# Arduino.net
KiCad netlist of a schematic drawn in Altium Designer
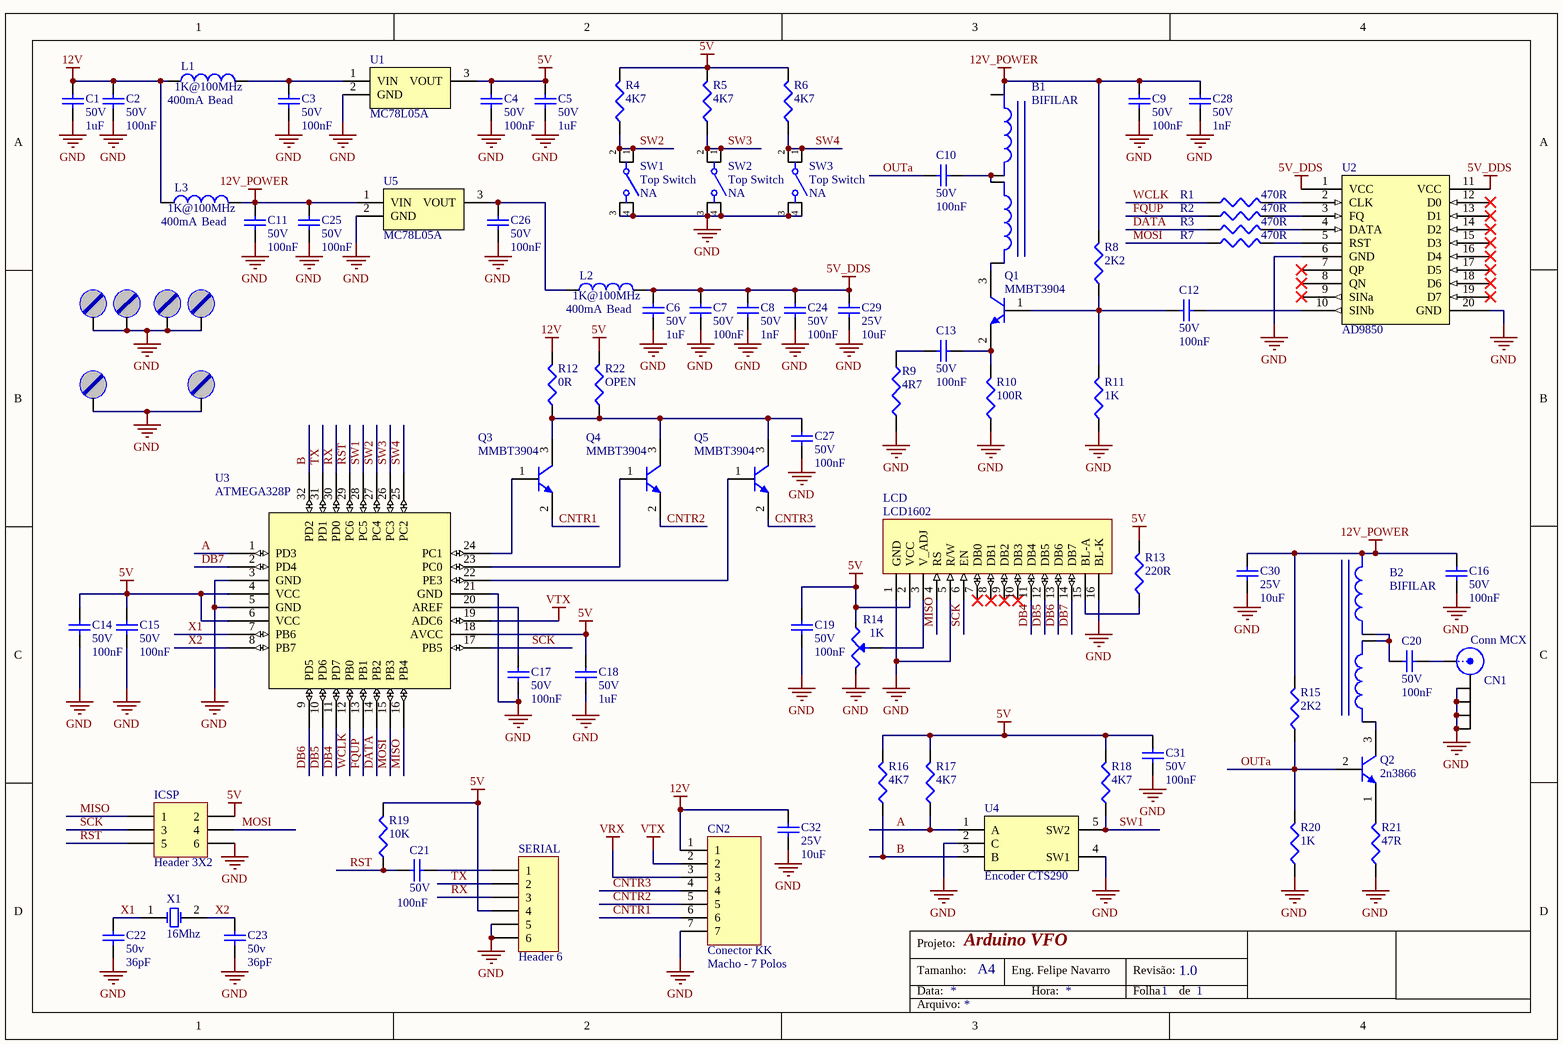
[diagram p0: Arduino.SchDoc]

(export (version "E")
  (design (tool "Eeschema 10.0.6"))
  (components
    (comp (ref "B1")
      (value "BIFILAR")
      (footprint "Toroid Bifilar")
      (description "Toroid Bifilar")
      (libsource (lib "") (part "Toroid Bifilar_1"))
    )
    (comp (ref "B2")
      (value "BIFILAR")
      (footprint "Toroid Bifilar")
      (description "Toroid Bifilar")
      (libsource (lib "NavarroIND") (part "Toroid Bifilar"))
    )
    (comp (ref "C1")
      (value "1uF")
      (footprint "CC0603")
      (description "Capacitor (Semiconductor SIM Model)")
      (fields (field (name "TENSÃO") "50V") (field (name "Comment") "Capacitor Cerâmico"))
      (libsource (lib "NavarroCAP") (part "Cap 1uF 50V 0603 X5R"))
    )
    (comp (ref "C2")
      (value "100nF")
      (footprint "CC0603")
      (description "Capacitor (Semiconductor SIM Model)")
      (fields (field (name "TENSÃO") "50V") (field (name "Comment") "Capacitor Cerâmico"))
      (libsource (lib "NavarroCAP") (part "Cap 100nF 50V 0603 X7R"))
    )
    (comp (ref "C3")
      (value "100nF")
      (footprint "CC0603")
      (description "Capacitor (Semiconductor SIM Model)")
      (fields (field (name "TENSÃO") "50V") (field (name "Comment") "Capacitor Cerâmico"))
      (libsource (lib "NavarroCAP") (part "Cap 100nF 50V 0603 X7R"))
    )
    (comp (ref "C4")
      (value "100nF")
      (footprint "CC0603")
      (description "Capacitor (Semiconductor SIM Model)")
      (fields (field (name "TENSÃO") "50V") (field (name "Comment") "Capacitor Cerâmico"))
      (libsource (lib "NavarroCAP") (part "Cap 100nF 50V 0603 X7R"))
    )
    (comp (ref "C5")
      (value "1uF")
      (footprint "CC0603")
      (description "Capacitor (Semiconductor SIM Model)")
      (fields (field (name "TENSÃO") "50V") (field (name "Comment") "Capacitor Cerâmico"))
      (libsource (lib "NavarroCAP") (part "Cap 1uF 50V 0603 X5R"))
    )
    (comp (ref "C6")
      (value "1uF")
      (footprint "CC0603")
      (description "Capacitor (Semiconductor SIM Model)")
      (fields (field (name "TENSÃO") "50V") (field (name "Comment") "Capacitor Cerâmico"))
      (libsource (lib "NavarroCAP") (part "Cap 1uF 50V 0603 X5R"))
    )
    (comp (ref "C7")
      (value "100nF")
      (footprint "CC0603")
      (description "Capacitor (Semiconductor SIM Model)")
      (fields (field (name "TENSÃO") "50V") (field (name "Comment") "Capacitor Cerâmico"))
      (libsource (lib "NavarroCAP") (part "Cap 100nF 50V 0603 X7R"))
    )
    (comp (ref "C8")
      (value "1nF")
      (footprint "CC0603")
      (description "Capacitor (Semiconductor SIM Model)")
      (fields (field (name "TENSÃO") "50V") (field (name "Comment") "Capacitor Cerâmico"))
      (libsource (lib "NavarroCAP") (part "Cap 1nF 50V 0603 NP0"))
    )
    (comp (ref "C9")
      (value "100nF")
      (footprint "CC0603")
      (description "Capacitor (Semiconductor SIM Model)")
      (fields (field (name "TENSÃO") "50V") (field (name "Comment") "Capacitor Cerâmico"))
      (libsource (lib "NavarroCAP") (part "Cap 100nF 50V 0603 X7R"))
    )
    (comp (ref "C10")
      (value "100nF")
      (footprint "CC0603")
      (description "Capacitor (Semiconductor SIM Model)")
      (fields (field (name "TENSÃO") "50V") (field (name "Comment") "Capacitor Cerâmico"))
      (libsource (lib "NavarroCAP") (part "Cap 100nF 50V 0603 X7R"))
    )
    (comp (ref "C11")
      (value "100nF")
      (footprint "CC0603")
      (description "Capacitor (Semiconductor SIM Model)")
      (fields (field (name "TENSÃO") "50V") (field (name "Comment") "Capacitor Cerâmico"))
      (libsource (lib "NavarroCAP") (part "Cap 100nF 50V 0603 X7R"))
    )
    (comp (ref "C12")
      (value "100nF")
      (footprint "CC0603")
      (description "Capacitor (Semiconductor SIM Model)")
      (fields (field (name "TENSÃO") "50V") (field (name "Comment") "Capacitor Cerâmico"))
      (libsource (lib "NavarroCAP") (part "Cap 100nF 50V 0603 X7R"))
    )
    (comp (ref "C13")
      (value "100nF")
      (footprint "CC0603")
      (description "Capacitor (Semiconductor SIM Model)")
      (fields (field (name "TENSÃO") "50V") (field (name "Comment") "Capacitor Cerâmico"))
      (libsource (lib "NavarroCAP") (part "Cap 100nF 50V 0603 X7R"))
    )
    (comp (ref "C14")
      (value "100nF")
      (footprint "CC0603")
      (description "Capacitor (Semiconductor SIM Model)")
      (fields (field (name "TENSÃO") "50V") (field (name "Comment") "Capacitor Cerâmico"))
      (libsource (lib "NavarroCAP") (part "Cap 100nF 50V 0603 X7R"))
    )
    (comp (ref "C15")
      (value "100nF")
      (footprint "CC0603")
      (description "Capacitor (Semiconductor SIM Model)")
      (fields (field (name "TENSÃO") "50V") (field (name "Comment") "Capacitor Cerâmico"))
      (libsource (lib "NavarroCAP") (part "Cap 100nF 50V 0603 X7R"))
    )
    (comp (ref "C16")
      (value "100nF")
      (footprint "CC0603")
      (description "Capacitor (Semiconductor SIM Model)")
      (fields (field (name "TENSÃO") "50V") (field (name "Comment") "Capacitor Cerâmico"))
      (libsource (lib "NavarroCAP") (part "Cap 100nF 50V 0603 X7R"))
    )
    (comp (ref "C17")
      (value "100nF")
      (footprint "CC0603")
      (description "Capacitor (Semiconductor SIM Model)")
      (fields (field (name "TENSÃO") "50V") (field (name "Comment") "Capacitor Cerâmico"))
      (libsource (lib "NavarroCAP") (part "Cap 100nF 50V 0603 X7R"))
    )
    (comp (ref "C18")
      (value "1uF")
      (footprint "CC0603")
      (description "Capacitor (Semiconductor SIM Model)")
      (fields (field (name "TENSÃO") "50V") (field (name "Comment") "Capacitor Cerâmico"))
      (libsource (lib "NavarroCAP") (part "Cap 1uF 50V 0603 X5R"))
    )
    (comp (ref "C19")
      (value "100nF")
      (footprint "CC0603")
      (description "Capacitor (Semiconductor SIM Model)")
      (fields (field (name "TENSÃO") "50V") (field (name "Comment") "Capacitor Cerâmico"))
      (libsource (lib "NavarroCAP") (part "Cap 100nF 50V 0603 X7R"))
    )
    (comp (ref "C20")
      (value "100nF")
      (footprint "CC0603")
      (description "Capacitor (Semiconductor SIM Model)")
      (fields (field (name "TENSÃO") "50V") (field (name "Comment") "Capacitor Cerâmico"))
      (libsource (lib "NavarroCAP") (part "Cap 100nF 50V 0603 X7R"))
    )
    (comp (ref "C21")
      (value "100nF")
      (footprint "CC0603")
      (description "Capacitor (Semiconductor SIM Model)")
      (fields (field (name "TENSÃO") "50V") (field (name "Comment") "Capacitor Cerâmico"))
      (libsource (lib "NavarroCAP") (part "Cap 100nF 50V 0603 X7R"))
    )
    (comp (ref "C22")
      (value "36pF")
      (footprint "CC0603")
      (description "Capacitor (Semiconductor SIM Model)")
      (fields (field (name "TENSÃO") "50v") (field (name "Comment") "Capacitor Cerâmico"))
      (libsource (lib "NavarroCAP") (part "Cap - $Val $V $Footprint $Classe_1"))
    )
    (comp (ref "C23")
      (value "36pF")
      (footprint "CC0603")
      (description "Capacitor (Semiconductor SIM Model)")
      (fields (field (name "TENSÃO") "50v") (field (name "Comment") "Capacitor Cerâmico"))
      (libsource (lib "NavarroCAP") (part "Cap - $Val $V $Footprint $Classe_1"))
    )
    (comp (ref "C24")
      (value "100nF")
      (footprint "CC0603")
      (description "Capacitor (Semiconductor SIM Model)")
      (fields (field (name "TENSÃO") "50V") (field (name "Comment") "Capacitor Cerâmico"))
      (libsource (lib "NavarroCAP") (part "Cap 100nF 50V 0603 X7R"))
    )
    (comp (ref "C25")
      (value "100nF")
      (footprint "CC0603")
      (description "Capacitor (Semiconductor SIM Model)")
      (fields (field (name "TENSÃO") "50V") (field (name "Comment") "Capacitor Cerâmico"))
      (libsource (lib "NavarroCAP") (part "Cap 100nF 50V 0603 X7R"))
    )
    (comp (ref "C26")
      (value "100nF")
      (footprint "CC0603")
      (description "Capacitor (Semiconductor SIM Model)")
      (fields (field (name "TENSÃO") "50V") (field (name "Comment") "Capacitor Cerâmico"))
      (libsource (lib "NavarroCAP") (part "Cap 100nF 50V 0603 X7R"))
    )
    (comp (ref "C27")
      (value "100nF")
      (footprint "CC0603")
      (description "Capacitor (Semiconductor SIM Model)")
      (fields (field (name "TENSÃO") "50V") (field (name "Comment") "Capacitor Cerâmico"))
      (libsource (lib "NavarroCAP") (part "Cap 100nF 50V 0603 X7R"))
    )
    (comp (ref "C28")
      (value "1nF")
      (footprint "CC0603")
      (description "Capacitor (Semiconductor SIM Model)")
      (fields (field (name "TENSÃO") "50V") (field (name "Comment") "Capacitor Cerâmico"))
      (libsource (lib "NavarroCAP") (part "Cap 100nF 50V 0603 X7R"))
    )
    (comp (ref "C29")
      (value "10uF")
      (footprint "CC0805")
      (description "Capacitor (Semiconductor SIM Model)")
      (fields (field (name "TENSÃO") "25V") (field (name "Comment") "Capacitor Cerâmico"))
      (libsource (lib "NavarroCAP") (part "Cap 10uF 25V 0805 X5R"))
    )
    (comp (ref "C30")
      (value "10uF")
      (footprint "CC0805")
      (description "Capacitor (Semiconductor SIM Model)")
      (fields (field (name "TENSÃO") "25V") (field (name "Comment") "Capacitor Cerâmico"))
      (libsource (lib "NavarroCAP") (part "Cap 10uF 25V 0805 X5R"))
    )
    (comp (ref "C31")
      (value "100nF")
      (footprint "CC0603")
      (description "Capacitor (Semiconductor SIM Model)")
      (fields (field (name "TENSÃO") "50V") (field (name "Comment") "Capacitor Cerâmico"))
      (libsource (lib "NavarroCAP") (part "Cap 100nF 50V 0603 X7R"))
    )
    (comp (ref "C32")
      (value "10uF")
      (footprint "CC0805")
      (description "Capacitor (Semiconductor SIM Model)")
      (fields (field (name "TENSÃO") "25V") (field (name "Comment") "Capacitor Cerâmico"))
      (libsource (lib "NavarroCAP") (part "Cap 10uF 25V 0805 X5R"))
    )
    (comp (ref "CN1")
      (value "Conn MCX")
      (footprint "CONN MCX MOLEX")
      (description "Conector MCX")
      (libsource (lib "NavarroCON") (part "Conn MCX"))
    )
    (comp (ref "CN2")
      (value "Conector KK")
      (footprint "CONN HDR7-POL P.100")
      (fields (field (name "ALTIUM_VALUE") "Macho - 7 Polos"))
      (libsource (lib "NavarroCON") (part "KK 7P Macho-V P2.54mm"))
    )
    (comp (ref "ICSP")
      (value "Header 3X2")
      (footprint "CONN HDR2X3")
      (description "Header, 5-Pin, Dual row")
      (libsource (lib "NavarroCON") (part "Header 3X2"))
    )
    (comp (ref "L1")
      (value "Bead")
      (footprint "CC0603")
      (fields (field (name "CORRENTE") "400mA") (field (name "ALTIUM_VALUE") "1K@100MHz"))
      (libsource (lib "NavarroIND") (part "Bd 1K@100MHz 0603 400mA"))
    )
    (comp (ref "L2")
      (value "Bead")
      (footprint "CC0603")
      (fields (field (name "CORRENTE") "400mA") (field (name "ALTIUM_VALUE") "1K@100MHz"))
      (libsource (lib "NavarroIND") (part "Bd 1K@100MHz 0603 400mA"))
    )
    (comp (ref "L3")
      (value "Bead")
      (footprint "CC0603")
      (fields (field (name "CORRENTE") "400mA") (field (name "ALTIUM_VALUE") "1K@100MHz"))
      (libsource (lib "NavarroIND") (part "Bd 1K@100MHz 0603 400mA"))
    )
    (comp (ref "LCD")
      (value "LCD1602")
      (footprint "LCD-1602")
      (description "LCD Generico 16 caracteres X 2 linhas")
      (libsource (lib "Navarro") (part "LCD1602"))
    )
    (comp (ref "M1")
      (value "Furo de Fixação")
      (footprint "Furo_M3")
      (description "Furo para parafuso")
      (libsource (lib "Tecnoclade") (part "Parafuso"))
    )
    (comp (ref "M2")
      (value "Furo de Fixação")
      (footprint "Furo_M3")
      (description "Furo para parafuso")
      (libsource (lib "Tecnoclade") (part "Parafuso"))
    )
    (comp (ref "M3")
      (value "Furo de Fixação")
      (footprint "Furo_M3")
      (description "Furo para parafuso")
      (libsource (lib "Tecnoclade") (part "Parafuso"))
    )
    (comp (ref "M4")
      (value "Furo de Fixação")
      (footprint "Furo_M3")
      (description "Furo para parafuso")
      (libsource (lib "Tecnoclade") (part "Parafuso"))
    )
    (comp (ref "M5")
      (value "Furo de Fixação")
      (footprint "Furo_M3")
      (description "Furo para parafuso")
      (libsource (lib "Tecnoclade") (part "Parafuso"))
    )
    (comp (ref "M6")
      (value "Furo de Fixação")
      (footprint "Furo_M3")
      (description "Furo para parafuso")
      (libsource (lib "Tecnoclade") (part "Parafuso"))
    )
    (comp (ref "Q1")
      (value "MMBT3904")
      (footprint "SOT-23-3N")
      (description "NPN General Purpose Amplifier")
      (libsource (lib "NavarroSEMI") (part "TRS MMBT3904 40V 200mA SOT-23-3N"))
    )
    (comp (ref "Q2")
      (value "2n3866")
      (footprint "TO-92R")
      (description "NPN General Purpose Amplifier")
      (libsource (lib "NavarroSEMI") (part "TRS BC108 TO-18"))
    )
    (comp (ref "Q3")
      (value "MMBT3904")
      (footprint "SOT-23-3N")
      (description "NPN General Purpose Amplifier")
      (libsource (lib "NavarroSEMI") (part "TRS MMBT3904 40V 200mA SOT-23-3N"))
    )
    (comp (ref "Q4")
      (value "MMBT3904")
      (footprint "SOT-23-3N")
      (description "NPN General Purpose Amplifier")
      (libsource (lib "NavarroSEMI") (part "TRS MMBT3904 40V 200mA SOT-23-3N"))
    )
    (comp (ref "Q5")
      (value "MMBT3904")
      (footprint "SOT-23-3N")
      (description "NPN General Purpose Amplifier")
      (libsource (lib "NavarroSEMI") (part "TRS MMBT3904 40V 200mA SOT-23-3N"))
    )
    (comp (ref "R1")
      (value "470R")
      (footprint "CC0603")
      (description "Resistor")
      (libsource (lib "NavarroRES") (part "Res 470R 5% 0603 1/10W"))
    )
    (comp (ref "R2")
      (value "470R")
      (footprint "CC0603")
      (description "Resistor")
      (libsource (lib "NavarroRES") (part "Res 470R 5% 0603 1/10W"))
    )
    (comp (ref "R3")
      (value "470R")
      (footprint "CC0603")
      (description "Resistor")
      (libsource (lib "NavarroRES") (part "Res 470R 5% 0603 1/10W"))
    )
    (comp (ref "R4")
      (value "4K7")
      (footprint "CC0603")
      (description "Resistor")
      (libsource (lib "NavarroRES") (part "Res 4K7 1% 0603 1/10W"))
    )
    (comp (ref "R5")
      (value "4K7")
      (footprint "CC0603")
      (description "Resistor")
      (libsource (lib "NavarroRES") (part "Res 4K7 1% 0603 1/10W"))
    )
    (comp (ref "R6")
      (value "4K7")
      (footprint "CC0603")
      (description "Resistor")
      (libsource (lib "NavarroRES") (part "Res 4K7 1% 0603 1/10W"))
    )
    (comp (ref "R7")
      (value "470R")
      (footprint "CC0603")
      (description "Resistor")
      (libsource (lib "NavarroRES") (part "Res 470R 5% 0603 1/10W"))
    )
    (comp (ref "R8")
      (value "2K2")
      (footprint "CC0603")
      (description "Resistor")
      (libsource (lib "NavarroRES") (part "Res 2K2 5% 0603 1/10W"))
    )
    (comp (ref "R9")
      (value "4R7")
      (footprint "CC0603")
      (description "Resistor")
      (libsource (lib "NavarroRES") (part "Res 4R7 1% 0603 1/10W"))
    )
    (comp (ref "R10")
      (value "100R")
      (footprint "CC0603")
      (description "Resistor")
      (libsource (lib "NavarroRES") (part "Res 100R 5% 0603 1/10W"))
    )
    (comp (ref "R11")
      (value "1K")
      (footprint "CC0603")
      (description "Resistor")
      (libsource (lib "NavarroRES") (part "Res 1K 1% 0603 1/10W"))
    )
    (comp (ref "R12")
      (value "0R")
      (footprint "CC0603")
      (description "Resistor")
      (libsource (lib "NavarroRES") (part "Res 0R 0603 1/10W"))
    )
    (comp (ref "R13")
      (value "220R")
      (footprint "CC0603")
      (description "Resistor")
      (libsource (lib "NavarroRES") (part "Res 220R 1% 0603 1/10W"))
    )
    (comp (ref "R14")
      (value "1K")
      (footprint "POT")
      (description "Potenciometro")
      (fields (field (name "Comment") "Potenciômetro"))
      (libsource (lib "NavarroRES") (part "Res Pot"))
    )
    (comp (ref "R15")
      (value "2K2")
      (footprint "CC0603")
      (description "Resistor")
      (libsource (lib "NavarroRES") (part "Res 2K2 5% 0603 1/10W"))
    )
    (comp (ref "R16")
      (value "4K7")
      (footprint "CC0603")
      (description "Resistor")
      (libsource (lib "NavarroRES") (part "Res 4K7 1% 0603 1/10W"))
    )
    (comp (ref "R17")
      (value "4K7")
      (footprint "CC0603")
      (description "Resistor")
      (libsource (lib "NavarroRES") (part "Res 4K7 1% 0603 1/10W"))
    )
    (comp (ref "R18")
      (value "4K7")
      (footprint "CC0603")
      (description "Resistor")
      (libsource (lib "NavarroRES") (part "Res 4K7 1% 0603 1/10W"))
    )
    (comp (ref "R19")
      (value "10K")
      (footprint "CC0603")
      (description "Resistor")
      (libsource (lib "NavarroRES") (part "Res 10K 1% 0603 1/10W"))
    )
    (comp (ref "R20")
      (value "1K")
      (footprint "CC0603")
      (description "Resistor")
      (libsource (lib "NavarroRES") (part "Res 1K 1% 0603 1/10W"))
    )
    (comp (ref "R21")
      (value "47R")
      (footprint "CC0603")
      (description "Resistor")
      (libsource (lib "NavarroRES") (part "Res 47K 1% 0603 1/10W"))
    )
    (comp (ref "R22")
      (value "OPEN")
      (footprint "CC0603")
      (description "Resistor")
      (libsource (lib "NavarroRES") (part "Res 0R 0603 1/10W"))
    )
    (comp (ref "SERIAL")
      (value "Header 6")
      (footprint "CONN HDR1X6")
      (description "Header, 6-Pin")
      (libsource (lib "NavarroCON") (part "Header 6"))
    )
    (comp (ref "SW1")
      (value "Top Switch")
      (footprint "SWITCH-TACTIL_6x6")
      (description "Single-Pole, Single-Throw Switch")
      (fields (field (name "ALTIUM_VALUE") "NA"))
      (libsource (lib "Tecnoclade") (part "SW-SPST Tactil"))
    )
    (comp (ref "SW2")
      (value "Top Switch")
      (footprint "SWITCH-TACTIL_6x6")
      (description "Single-Pole, Single-Throw Switch")
      (fields (field (name "ALTIUM_VALUE") "NA"))
      (libsource (lib "Tecnoclade") (part "SW-SPST Tactil"))
    )
    (comp (ref "SW3")
      (value "Top Switch")
      (footprint "SWITCH-TACTIL_6x6")
      (description "Single-Pole, Single-Throw Switch")
      (fields (field (name "ALTIUM_VALUE") "NA"))
      (libsource (lib "Tecnoclade") (part "SW-SPST Tactil"))
    )
    (comp (ref "U1")
      (value "MC78L05A")
      (footprint "SOT-89-3N")
      (description "Regulador Linear 5V")
      (libsource (lib "Navarro") (part "MC78L05"))
    )
    (comp (ref "U2")
      (value "AD9850")
      (footprint "AD9850")
      (description "DDS AD9850 Module")
      (libsource (lib "Navarro") (part "AD9850"))
    )
    (comp (ref "U3")
      (value "ATMEGA328P")
      (footprint "TQFP-32N")
      (description "IC MCU 32KB FLASH 20MHZ 32TQFP")
      (libsource (lib "Navarro") (part "ATMEGA328P"))
    )
    (comp (ref "U4")
      (value "Encoder CTS290")
      (footprint "ENCODER - CTS 290")
      (description "Memória")
      (libsource (lib "Navarro") (part "Encoder CTS 290"))
    )
    (comp (ref "U5")
      (value "MC78L05A")
      (footprint "SOT-89-3N")
      (description "Regulador Linear 5V")
      (libsource (lib "Navarro") (part "MC78L05"))
    )
    (comp (ref "X1")
      (value "16Mhz")
      (footprint "HC/49US")
      (description "Crystal Oscillator")
      (libsource (lib "Navarro") (part "XTAL"))
    )
  )
  (nets
    (net (code "1") (name "/A") (class "Default")
      (node (ref "R17") (pin "1") (pinfunction "1_1") (pintype "passive"))
      (node (ref "U3") (pin "1") (pinfunction "PD3_1") (pintype "bidirectional"))
      (node (ref "U4") (pin "1") (pinfunction "A_1") (pintype "passive"))
    )
    (net (code "2") (name "/B") (class "Default")
      (node (ref "R16") (pin "1") (pinfunction "1_1") (pintype "passive"))
      (node (ref "U3") (pin "32") (pinfunction "PD2_32") (pintype "bidirectional"))
      (node (ref "U4") (pin "3") (pinfunction "B_3") (pintype "passive"))
    )
    (net (code "3") (name "/CNTR1") (class "Default")
      (node (ref "CN2") (pin "6") (pinfunction "6_6") (pintype "passive"))
      (node (ref "Q3") (pin "2") (pinfunction "E_2") (pintype "passive"))
    )
    (net (code "4") (name "/CNTR2") (class "Default")
      (node (ref "CN2") (pin "5") (pinfunction "5_5") (pintype "passive"))
      (node (ref "Q4") (pin "2") (pinfunction "E_2") (pintype "passive"))
    )
    (net (code "5") (name "/CNTR3") (class "Default")
      (node (ref "CN2") (pin "4") (pinfunction "4_4") (pintype "passive"))
      (node (ref "Q5") (pin "2") (pinfunction "E_2") (pintype "passive"))
    )
    (net (code "6") (name "/DATA") (class "Default")
      (node (ref "R3") (pin "1") (pinfunction "1_1") (pintype "passive"))
      (node (ref "U3") (pin "14") (pinfunction "PB2_14") (pintype "bidirectional"))
    )
    (net (code "7") (name "/DB4") (class "Default")
      (node (ref "LCD") (pin "11") (pinfunction "DB4_11") (pintype "bidirectional"))
      (node (ref "U3") (pin "11") (pinfunction "PD7_11") (pintype "bidirectional"))
    )
    (net (code "8") (name "/DB5") (class "Default")
      (node (ref "LCD") (pin "12") (pinfunction "DB5_12") (pintype "bidirectional"))
      (node (ref "U3") (pin "10") (pinfunction "PD6_10") (pintype "bidirectional"))
    )
    (net (code "9") (name "/DB6") (class "Default")
      (node (ref "LCD") (pin "13") (pinfunction "DB6_13") (pintype "bidirectional"))
      (node (ref "U3") (pin "9") (pinfunction "PD5_9") (pintype "bidirectional"))
    )
    (net (code "10") (name "/DB7") (class "Default")
      (node (ref "LCD") (pin "14") (pinfunction "DB7_14") (pintype "bidirectional"))
      (node (ref "U3") (pin "2") (pinfunction "PD4_2") (pintype "bidirectional"))
    )
    (net (code "11") (name "/FQUP") (class "Default")
      (node (ref "R2") (pin "1") (pinfunction "1_1") (pintype "passive"))
      (node (ref "U3") (pin "13") (pinfunction "PB1_13") (pintype "bidirectional"))
    )
    (net (code "12") (name "/MISO") (class "Default")
      (node (ref "ICSP") (pin "1") (pinfunction "1_1") (pintype "passive"))
      (node (ref "LCD") (pin "4") (pinfunction "RS_4") (pintype "input"))
      (node (ref "U3") (pin "16") (pinfunction "PB4_16") (pintype "bidirectional"))
    )
    (net (code "13") (name "/MOSI") (class "Default")
      (node (ref "ICSP") (pin "4") (pinfunction "4_4") (pintype "passive"))
      (node (ref "R7") (pin "1") (pinfunction "1_1") (pintype "passive"))
      (node (ref "U3") (pin "15") (pinfunction "PB3_15") (pintype "bidirectional"))
    )
    (net (code "14") (name "/OUTa") (class "Default")
      (node (ref "C10") (pin "2") (pinfunction "2_2") (pintype "passive"))
      (node (ref "Q2") (pin "2") (pinfunction "B_2") (pintype "passive"))
      (node (ref "R15") (pin "1") (pinfunction "1_1") (pintype "passive"))
      (node (ref "R20") (pin "2") (pinfunction "2_2") (pintype "passive"))
    )
    (net (code "15") (name "/RST") (class "Default")
      (node (ref "C21") (pin "2") (pinfunction "2_2") (pintype "passive"))
      (node (ref "ICSP") (pin "5") (pinfunction "5_5") (pintype "passive"))
      (node (ref "R19") (pin "1") (pinfunction "1_1") (pintype "passive"))
      (node (ref "U3") (pin "29") (pinfunction "PC6_29") (pintype "bidirectional"))
    )
    (net (code "16") (name "/RX") (class "Default")
      (node (ref "SERIAL") (pin "3") (pinfunction "3_3") (pintype "passive"))
      (node (ref "U3") (pin "30") (pinfunction "PD0_30") (pintype "bidirectional"))
    )
    (net (code "17") (name "/SCK") (class "Default")
      (node (ref "ICSP") (pin "3") (pinfunction "3_3") (pintype "passive"))
      (node (ref "LCD") (pin "6") (pinfunction "EN_6") (pintype "input"))
      (node (ref "U3") (pin "17") (pinfunction "PB5_17") (pintype "bidirectional"))
    )
    (net (code "18") (name "/SW1") (class "Default")
      (node (ref "R18") (pin "1") (pinfunction "1_1") (pintype "passive"))
      (node (ref "U3") (pin "28") (pinfunction "PC5_28") (pintype "bidirectional"))
      (node (ref "U4") (pin "5") (pinfunction "SW2_5") (pintype "passive"))
    )
    (net (code "19") (name "/SW2") (class "Default")
      (node (ref "R4") (pin "1") (pinfunction "1_1") (pintype "passive"))
      (node (ref "SW1") (pin "1") (pinfunction "1_1") (pintype "tri_state"))
      (node (ref "SW1") (pin "2") (pinfunction "2_2") (pintype "tri_state"))
      (node (ref "U3") (pin "27") (pinfunction "PC4_27") (pintype "bidirectional"))
    )
    (net (code "20") (name "/SW3") (class "Default")
      (node (ref "R5") (pin "1") (pinfunction "1_1") (pintype "passive"))
      (node (ref "SW2") (pin "1") (pinfunction "1_1") (pintype "tri_state"))
      (node (ref "SW2") (pin "2") (pinfunction "2_2") (pintype "tri_state"))
      (node (ref "U3") (pin "26") (pinfunction "PC3_26") (pintype "bidirectional"))
    )
    (net (code "21") (name "/SW4") (class "Default")
      (node (ref "R6") (pin "1") (pinfunction "1_1") (pintype "passive"))
      (node (ref "SW3") (pin "1") (pinfunction "1_1") (pintype "tri_state"))
      (node (ref "SW3") (pin "2") (pinfunction "2_2") (pintype "tri_state"))
      (node (ref "U3") (pin "25") (pinfunction "PC2_25") (pintype "bidirectional"))
    )
    (net (code "22") (name "/TX") (class "Default")
      (node (ref "SERIAL") (pin "2") (pinfunction "2_2") (pintype "passive"))
      (node (ref "U3") (pin "31") (pinfunction "PD1_31") (pintype "bidirectional"))
    )
    (net (code "23") (name "/WCLK") (class "Default")
      (node (ref "R1") (pin "1") (pinfunction "1_1") (pintype "passive"))
      (node (ref "U3") (pin "12") (pinfunction "PB0_12") (pintype "bidirectional"))
    )
    (net (code "24") (name "/X1") (class "Default")
      (node (ref "C22") (pin "2") (pinfunction "2_2") (pintype "passive"))
      (node (ref "U3") (pin "7") (pinfunction "PB6_7") (pintype "bidirectional"))
      (node (ref "X1") (pin "1") (pinfunction "OSC1_1") (pintype "passive"))
    )
    (net (code "25") (name "/X2") (class "Default")
      (node (ref "C23") (pin "2") (pinfunction "2_2") (pintype "passive"))
      (node (ref "U3") (pin "8") (pinfunction "PB7_8") (pintype "bidirectional"))
      (node (ref "X1") (pin "2") (pinfunction "OSC2_2") (pintype "passive"))
    )
    (net (code "26") (name "5V") (class "Default")
      (node (ref "C14") (pin "2") (pinfunction "2_2") (pintype "passive"))
      (node (ref "C15") (pin "2") (pinfunction "2_2") (pintype "passive"))
      (node (ref "C18") (pin "2") (pinfunction "2_2") (pintype "passive"))
      (node (ref "C19") (pin "2") (pinfunction "2_2") (pintype "passive"))
      (node (ref "C31") (pin "2") (pinfunction "2_2") (pintype "passive"))
      (node (ref "C4") (pin "2") (pinfunction "2_2") (pintype "passive"))
      (node (ref "C5") (pin "2") (pinfunction "2_2") (pintype "passive"))
      (node (ref "ICSP") (pin "2") (pinfunction "2_2") (pintype "passive"))
      (node (ref "LCD") (pin "2") (pinfunction "VCC_2") (pintype "power_in"))
      (node (ref "R13") (pin "2") (pinfunction "2_2") (pintype "passive"))
      (node (ref "R14") (pin "1") (pinfunction "1_1") (pintype "passive"))
      (node (ref "R16") (pin "2") (pinfunction "2_2") (pintype "passive"))
      (node (ref "R17") (pin "2") (pinfunction "2_2") (pintype "passive"))
      (node (ref "R18") (pin "2") (pinfunction "2_2") (pintype "passive"))
      (node (ref "R19") (pin "2") (pinfunction "2_2") (pintype "passive"))
      (node (ref "R22") (pin "2") (pinfunction "2_2") (pintype "passive"))
      (node (ref "R4") (pin "2") (pinfunction "2_2") (pintype "passive"))
      (node (ref "R5") (pin "2") (pinfunction "2_2") (pintype "passive"))
      (node (ref "R6") (pin "2") (pinfunction "2_2") (pintype "passive"))
      (node (ref "SERIAL") (pin "4") (pinfunction "4_4") (pintype "passive"))
      (node (ref "U1") (pin "3") (pinfunction "VOUT_3") (pintype "power_in"))
      (node (ref "U3") (pin "18") (pinfunction "AVCC_18") (pintype "power_in"))
      (node (ref "U3") (pin "4") (pinfunction "VCC_4") (pintype "power_in"))
      (node (ref "U3") (pin "6") (pinfunction "VCC_6") (pintype "power_in"))
    )
    (net (code "27") (name "5V_DDS") (class "Default")
      (node (ref "C24") (pin "2") (pinfunction "2_2") (pintype "passive"))
      (node (ref "C29") (pin "2") (pinfunction "2_2") (pintype "passive"))
      (node (ref "C6") (pin "2") (pinfunction "2_2") (pintype "passive"))
      (node (ref "C7") (pin "2") (pinfunction "2_2") (pintype "passive"))
      (node (ref "C8") (pin "2") (pinfunction "2_2") (pintype "passive"))
      (node (ref "L2") (pin "2") (pinfunction "2_2") (pintype "passive"))
      (node (ref "U2") (pin "1") (pinfunction "VCC_1") (pintype "power_in"))
      (node (ref "U2") (pin "11") (pinfunction "VCC_11") (pintype "power_in"))
    )
    (net (code "28") (name "12V") (class "Default")
      (node (ref "C1") (pin "2") (pinfunction "2_2") (pintype "passive"))
      (node (ref "C2") (pin "2") (pinfunction "2_2") (pintype "passive"))
      (node (ref "C32") (pin "2") (pinfunction "2_2") (pintype "passive"))
      (node (ref "CN2") (pin "1") (pinfunction "1_1") (pintype "passive"))
      (node (ref "L1") (pin "1") (pinfunction "1_1") (pintype "passive"))
      (node (ref "L3") (pin "1") (pinfunction "1_1") (pintype "passive"))
      (node (ref "R12") (pin "2") (pinfunction "2_2") (pintype "passive"))
    )
    (net (code "29") (name "12V_POWER") (class "Default")
      (node (ref "B1") (pin "1") (pinfunction "Pri+_1") (pintype "passive"))
      (node (ref "B2") (pin "1") (pinfunction "Pri+_1") (pintype "passive"))
      (node (ref "C11") (pin "2") (pinfunction "2_2") (pintype "passive"))
      (node (ref "C16") (pin "2") (pinfunction "2_2") (pintype "passive"))
      (node (ref "C25") (pin "2") (pinfunction "2_2") (pintype "passive"))
      (node (ref "C28") (pin "2") (pinfunction "2_2") (pintype "passive"))
      (node (ref "C30") (pin "2") (pinfunction "2_2") (pintype "passive"))
      (node (ref "C9") (pin "2") (pinfunction "2_2") (pintype "passive"))
      (node (ref "L3") (pin "2") (pinfunction "2_2") (pintype "passive"))
      (node (ref "R15") (pin "2") (pinfunction "2_2") (pintype "passive"))
      (node (ref "R8") (pin "2") (pinfunction "2_2") (pintype "passive"))
      (node (ref "U5") (pin "1") (pinfunction "VIN_1") (pintype "power_in"))
    )
    (net (code "30") (name "GND") (class "Default")
      (node (ref "C1") (pin "1") (pinfunction "1_1") (pintype "passive"))
      (node (ref "C11") (pin "1") (pinfunction "1_1") (pintype "passive"))
      (node (ref "C14") (pin "1") (pinfunction "1_1") (pintype "passive"))
      (node (ref "C15") (pin "1") (pinfunction "1_1") (pintype "passive"))
      (node (ref "C16") (pin "1") (pinfunction "1_1") (pintype "passive"))
      (node (ref "C17") (pin "1") (pinfunction "1_1") (pintype "passive"))
      (node (ref "C18") (pin "1") (pinfunction "1_1") (pintype "passive"))
      (node (ref "C19") (pin "1") (pinfunction "1_1") (pintype "passive"))
      (node (ref "C2") (pin "1") (pinfunction "1_1") (pintype "passive"))
      (node (ref "C22") (pin "1") (pinfunction "1_1") (pintype "passive"))
      (node (ref "C23") (pin "1") (pinfunction "1_1") (pintype "passive"))
      (node (ref "C24") (pin "1") (pinfunction "1_1") (pintype "passive"))
      (node (ref "C25") (pin "1") (pinfunction "1_1") (pintype "passive"))
      (node (ref "C26") (pin "1") (pinfunction "1_1") (pintype "passive"))
      (node (ref "C27") (pin "1") (pinfunction "1_1") (pintype "passive"))
      (node (ref "C28") (pin "1") (pinfunction "1_1") (pintype "passive"))
      (node (ref "C29") (pin "1") (pinfunction "1_1") (pintype "passive"))
      (node (ref "C3") (pin "1") (pinfunction "1_1") (pintype "passive"))
      (node (ref "C30") (pin "1") (pinfunction "1_1") (pintype "passive"))
      (node (ref "C31") (pin "1") (pinfunction "1_1") (pintype "passive"))
      (node (ref "C32") (pin "1") (pinfunction "1_1") (pintype "passive"))
      (node (ref "C4") (pin "1") (pinfunction "1_1") (pintype "passive"))
      (node (ref "C5") (pin "1") (pinfunction "1_1") (pintype "passive"))
      (node (ref "C6") (pin "1") (pinfunction "1_1") (pintype "passive"))
      (node (ref "C7") (pin "1") (pinfunction "1_1") (pintype "passive"))
      (node (ref "C8") (pin "1") (pinfunction "1_1") (pintype "passive"))
      (node (ref "C9") (pin "1") (pinfunction "1_1") (pintype "passive"))
      (node (ref "CN1") (pin "2") (pinfunction "Y_2") (pintype "passive"))
      (node (ref "CN1") (pin "3") (pinfunction "Y_3") (pintype "passive"))
      (node (ref "CN1") (pin "4") (pinfunction "Y_4") (pintype "passive"))
      (node (ref "CN1") (pin "5") (pinfunction "Y_5") (pintype "passive"))
      (node (ref "CN2") (pin "7") (pinfunction "7_7") (pintype "passive"))
      (node (ref "ICSP") (pin "6") (pinfunction "6_6") (pintype "passive"))
      (node (ref "LCD") (pin "1") (pinfunction "GND_1") (pintype "power_in"))
      (node (ref "LCD") (pin "16") (pinfunction "BL-K_16") (pintype "passive"))
      (node (ref "LCD") (pin "5") (pinfunction "R/W_5") (pintype "input"))
      (node (ref "M1") (pin "X") (pinfunction "X_X") (pintype "passive"))
      (node (ref "M2") (pin "X") (pinfunction "X_X") (pintype "passive"))
      (node (ref "M3") (pin "X") (pinfunction "X_X") (pintype "passive"))
      (node (ref "M4") (pin "X") (pinfunction "X_X") (pintype "passive"))
      (node (ref "M5") (pin "X") (pinfunction "X_X") (pintype "passive"))
      (node (ref "M6") (pin "X") (pinfunction "X_X") (pintype "passive"))
      (node (ref "R10") (pin "1") (pinfunction "1_1") (pintype "passive"))
      (node (ref "R11") (pin "1") (pinfunction "1_1") (pintype "passive"))
      (node (ref "R14") (pin "3") (pinfunction "3_3") (pintype "passive"))
      (node (ref "R20") (pin "1") (pinfunction "1_1") (pintype "passive"))
      (node (ref "R21") (pin "1") (pinfunction "1_1") (pintype "passive"))
      (node (ref "R9") (pin "1") (pinfunction "1_1") (pintype "passive"))
      (node (ref "SERIAL") (pin "5") (pinfunction "5_5") (pintype "passive"))
      (node (ref "SERIAL") (pin "6") (pinfunction "6_6") (pintype "passive"))
      (node (ref "SW1") (pin "3") (pinfunction "3_3") (pintype "tri_state"))
      (node (ref "SW1") (pin "4") (pinfunction "4_4") (pintype "tri_state"))
      (node (ref "SW2") (pin "3") (pinfunction "3_3") (pintype "tri_state"))
      (node (ref "SW2") (pin "4") (pinfunction "4_4") (pintype "tri_state"))
      (node (ref "SW3") (pin "3") (pinfunction "3_3") (pintype "tri_state"))
      (node (ref "SW3") (pin "4") (pinfunction "4_4") (pintype "tri_state"))
      (node (ref "U1") (pin "2") (pinfunction "GND_2") (pintype "power_in"))
      (node (ref "U2") (pin "20") (pinfunction "GND_20") (pintype "power_in"))
      (node (ref "U2") (pin "6") (pinfunction "GND_6") (pintype "power_in"))
      (node (ref "U3") (pin "21") (pinfunction "GND_21") (pintype "power_in"))
      (node (ref "U3") (pin "3") (pinfunction "GND_3") (pintype "power_in"))
      (node (ref "U3") (pin "5") (pinfunction "GND_5") (pintype "power_in"))
      (node (ref "U4") (pin "2") (pinfunction "C_2") (pintype "passive"))
      (node (ref "U4") (pin "4") (pinfunction "SW1_4") (pintype "power_in"))
      (node (ref "U5") (pin "2") (pinfunction "GND_2") (pintype "power_in"))
    )
    (net (code "31") (name "Net-(B1-Pri-)") (class "Default")
      (node (ref "B1") (pin "4") (pinfunction "Pri-_4") (pintype "passive"))
      (node (ref "Q1") (pin "3") (pinfunction "C_3") (pintype "passive"))
    )
    (net (code "32") (name "Net-(B1-Sec+)") (class "Default")
      (node (ref "B1") (pin "2") (pinfunction "Sec-_2") (pintype "passive"))
      (node (ref "B1") (pin "3") (pinfunction "Sec+_3") (pintype "passive"))
      (node (ref "C10") (pin "1") (pinfunction "1_1") (pintype "passive"))
    )
    (net (code "33") (name "Net-(B2-Pri-)") (class "Default")
      (node (ref "B2") (pin "4") (pinfunction "Pri-_4") (pintype "passive"))
      (node (ref "Q2") (pin "3") (pinfunction "C_3") (pintype "passive"))
    )
    (net (code "34") (name "Net-(B2-Sec+)") (class "Default")
      (node (ref "B2") (pin "2") (pinfunction "Sec-_2") (pintype "passive"))
      (node (ref "B2") (pin "3") (pinfunction "Sec+_3") (pintype "passive"))
      (node (ref "C20") (pin "2") (pinfunction "2_2") (pintype "passive"))
    )
    (net (code "35") (name "Net-(C13-Pad1)") (class "Default")
      (node (ref "C13") (pin "1") (pinfunction "1_1") (pintype "passive"))
      (node (ref "R9") (pin "2") (pinfunction "2_2") (pintype "passive"))
    )
    (net (code "36") (name "Net-(C21-Pad1)") (class "Default")
      (node (ref "C21") (pin "1") (pinfunction "1_1") (pintype "passive"))
      (node (ref "SERIAL") (pin "1") (pinfunction "1_1") (pintype "passive"))
    )
    (net (code "37") (name "Net-(CN1-X)") (class "Default")
      (node (ref "C20") (pin "1") (pinfunction "1_1") (pintype "passive"))
      (node (ref "CN1") (pin "1") (pinfunction "X_1") (pintype "passive"))
    )
    (net (code "38") (name "Net-(LCD-BL-A)") (class "Default")
      (node (ref "LCD") (pin "15") (pinfunction "BL-A_15") (pintype "passive"))
      (node (ref "R13") (pin "1") (pinfunction "1_1") (pintype "passive"))
    )
    (net (code "39") (name "Net-(LCD-V_ADJ)") (class "Default")
      (node (ref "LCD") (pin "3") (pinfunction "V_ADJ_3") (pintype "power_in"))
      (node (ref "R14") (pin "2") (pinfunction "TAP_2") (pintype "passive"))
    )
    (net (code "40") (name "Net-(Q1-B)") (class "Default")
      (node (ref "C12") (pin "2") (pinfunction "2_2") (pintype "passive"))
      (node (ref "Q1") (pin "1") (pinfunction "B_1") (pintype "passive"))
      (node (ref "R11") (pin "2") (pinfunction "2_2") (pintype "passive"))
      (node (ref "R8") (pin "1") (pinfunction "1_1") (pintype "passive"))
    )
    (net (code "41") (name "Net-(Q1-E)") (class "Default")
      (node (ref "C13") (pin "2") (pinfunction "2_2") (pintype "passive"))
      (node (ref "Q1") (pin "2") (pinfunction "E_2") (pintype "passive"))
      (node (ref "R10") (pin "2") (pinfunction "2_2") (pintype "passive"))
    )
    (net (code "42") (name "Net-(Q2-E)") (class "Default")
      (node (ref "Q2") (pin "1") (pinfunction "E_1") (pintype "passive"))
      (node (ref "R21") (pin "2") (pinfunction "2_2") (pintype "passive"))
    )
    (net (code "43") (name "Net-(Q3-B)") (class "Default")
      (node (ref "Q3") (pin "1") (pinfunction "B_1") (pintype "passive"))
      (node (ref "U3") (pin "24") (pinfunction "PC1_24") (pintype "bidirectional"))
    )
    (net (code "44") (name "Net-(Q3-C)") (class "Default")
      (node (ref "C27") (pin "2") (pinfunction "2_2") (pintype "passive"))
      (node (ref "Q3") (pin "3") (pinfunction "C_3") (pintype "passive"))
      (node (ref "Q4") (pin "3") (pinfunction "C_3") (pintype "passive"))
      (node (ref "Q5") (pin "3") (pinfunction "C_3") (pintype "passive"))
      (node (ref "R12") (pin "1") (pinfunction "1_1") (pintype "passive"))
      (node (ref "R22") (pin "1") (pinfunction "1_1") (pintype "passive"))
    )
    (net (code "45") (name "Net-(Q4-B)") (class "Default")
      (node (ref "Q4") (pin "1") (pinfunction "B_1") (pintype "passive"))
      (node (ref "U3") (pin "23") (pinfunction "PC0_23") (pintype "bidirectional"))
    )
    (net (code "46") (name "Net-(Q5-B)") (class "Default")
      (node (ref "Q5") (pin "1") (pinfunction "B_1") (pintype "passive"))
      (node (ref "U3") (pin "22") (pinfunction "PE3_22") (pintype "bidirectional"))
    )
    (net (code "47") (name "Net-(U1-VIN)") (class "Default")
      (node (ref "C3") (pin "2") (pinfunction "2_2") (pintype "passive"))
      (node (ref "L1") (pin "2") (pinfunction "2_2") (pintype "passive"))
      (node (ref "U1") (pin "1") (pinfunction "VIN_1") (pintype "power_in"))
    )
    (net (code "48") (name "Net-(U2-CLK)") (class "Default")
      (node (ref "R1") (pin "2") (pinfunction "2_2") (pintype "passive"))
      (node (ref "U2") (pin "2") (pinfunction "CLK_2") (pintype "input"))
    )
    (net (code "49") (name "Net-(U2-DATA)") (class "Default")
      (node (ref "R3") (pin "2") (pinfunction "2_2") (pintype "passive"))
      (node (ref "U2") (pin "4") (pinfunction "DATA_4") (pintype "input"))
    )
    (net (code "50") (name "Net-(U2-FQ)") (class "Default")
      (node (ref "R2") (pin "2") (pinfunction "2_2") (pintype "passive"))
      (node (ref "U2") (pin "3") (pinfunction "FQ_3") (pintype "input"))
    )
    (net (code "51") (name "Net-(U2-RST)") (class "Default")
      (node (ref "R7") (pin "2") (pinfunction "2_2") (pintype "passive"))
      (node (ref "U2") (pin "5") (pinfunction "RST_5") (pintype "power_in"))
    )
    (net (code "52") (name "Net-(U2-SINb)") (class "Default")
      (node (ref "C12") (pin "1") (pinfunction "1_1") (pintype "passive"))
      (node (ref "U2") (pin "10") (pinfunction "SINb_10") (pintype "output"))
    )
    (net (code "53") (name "Net-(U3-AREF)") (class "Default")
      (node (ref "C17") (pin "2") (pinfunction "2_2") (pintype "passive"))
      (node (ref "U3") (pin "20") (pinfunction "AREF_20") (pintype "passive"))
    )
    (net (code "54") (name "Net-(U5-VOUT)") (class "Default")
      (node (ref "C26") (pin "2") (pinfunction "2_2") (pintype "passive"))
      (node (ref "L2") (pin "1") (pinfunction "1_1") (pintype "passive"))
      (node (ref "U5") (pin "3") (pinfunction "VOUT_3") (pintype "power_in"))
    )
    (net (code "55") (name "VRX") (class "Default")
      (node (ref "CN2") (pin "3") (pinfunction "3_3") (pintype "passive"))
    )
    (net (code "56") (name "VTX") (class "Default")
      (node (ref "CN2") (pin "2") (pinfunction "2_2") (pintype "passive"))
      (node (ref "U3") (pin "19") (pinfunction "ADC6_19") (pintype "bidirectional"))
    )
    (net (code "57") (name "unconnected-(LCD-DB0-Pad7)") (class "Default")
      (node (ref "LCD") (pin "7") (pinfunction "DB0_7") (pintype "bidirectional+no_connect"))
    )
    (net (code "58") (name "unconnected-(LCD-DB1-Pad8)") (class "Default")
      (node (ref "LCD") (pin "8") (pinfunction "DB1_8") (pintype "bidirectional+no_connect"))
    )
    (net (code "59") (name "unconnected-(LCD-DB2-Pad9)") (class "Default")
      (node (ref "LCD") (pin "9") (pinfunction "DB2_9") (pintype "bidirectional+no_connect"))
    )
    (net (code "60") (name "unconnected-(LCD-DB3-Pad10)") (class "Default")
      (node (ref "LCD") (pin "10") (pinfunction "DB3_10") (pintype "bidirectional+no_connect"))
    )
    (net (code "61") (name "unconnected-(U2-D0-Pad12)") (class "Default")
      (node (ref "U2") (pin "12") (pinfunction "D0_12") (pintype "input+no_connect"))
    )
    (net (code "62") (name "unconnected-(U2-D1-Pad13)") (class "Default")
      (node (ref "U2") (pin "13") (pinfunction "D1_13") (pintype "input+no_connect"))
    )
    (net (code "63") (name "unconnected-(U2-D2-Pad14)") (class "Default")
      (node (ref "U2") (pin "14") (pinfunction "D2_14") (pintype "input+no_connect"))
    )
    (net (code "64") (name "unconnected-(U2-D3-Pad15)") (class "Default")
      (node (ref "U2") (pin "15") (pinfunction "D3_15") (pintype "input+no_connect"))
    )
    (net (code "65") (name "unconnected-(U2-D4-Pad16)") (class "Default")
      (node (ref "U2") (pin "16") (pinfunction "D4_16") (pintype "input+no_connect"))
    )
    (net (code "66") (name "unconnected-(U2-D5-Pad17)") (class "Default")
      (node (ref "U2") (pin "17") (pinfunction "D5_17") (pintype "input+no_connect"))
    )
    (net (code "67") (name "unconnected-(U2-D6-Pad18)") (class "Default")
      (node (ref "U2") (pin "18") (pinfunction "D6_18") (pintype "input+no_connect"))
    )
    (net (code "68") (name "unconnected-(U2-D7-Pad19)") (class "Default")
      (node (ref "U2") (pin "19") (pinfunction "D7_19") (pintype "input+no_connect"))
    )
    (net (code "69") (name "unconnected-(U2-QN-Pad8)") (class "Default")
      (node (ref "U2") (pin "8") (pinfunction "QN_8") (pintype "passive+no_connect"))
    )
    (net (code "70") (name "unconnected-(U2-QP-Pad7)") (class "Default")
      (node (ref "U2") (pin "7") (pinfunction "QP_7") (pintype "passive+no_connect"))
    )
    (net (code "71") (name "unconnected-(U2-SINa-Pad9)") (class "Default")
      (node (ref "U2") (pin "9") (pinfunction "SINa_9") (pintype "output+no_connect"))
    )
  )
)
